# STM32F103C8T6.net
KiCad netlist of a schematic drawn in EAGLE
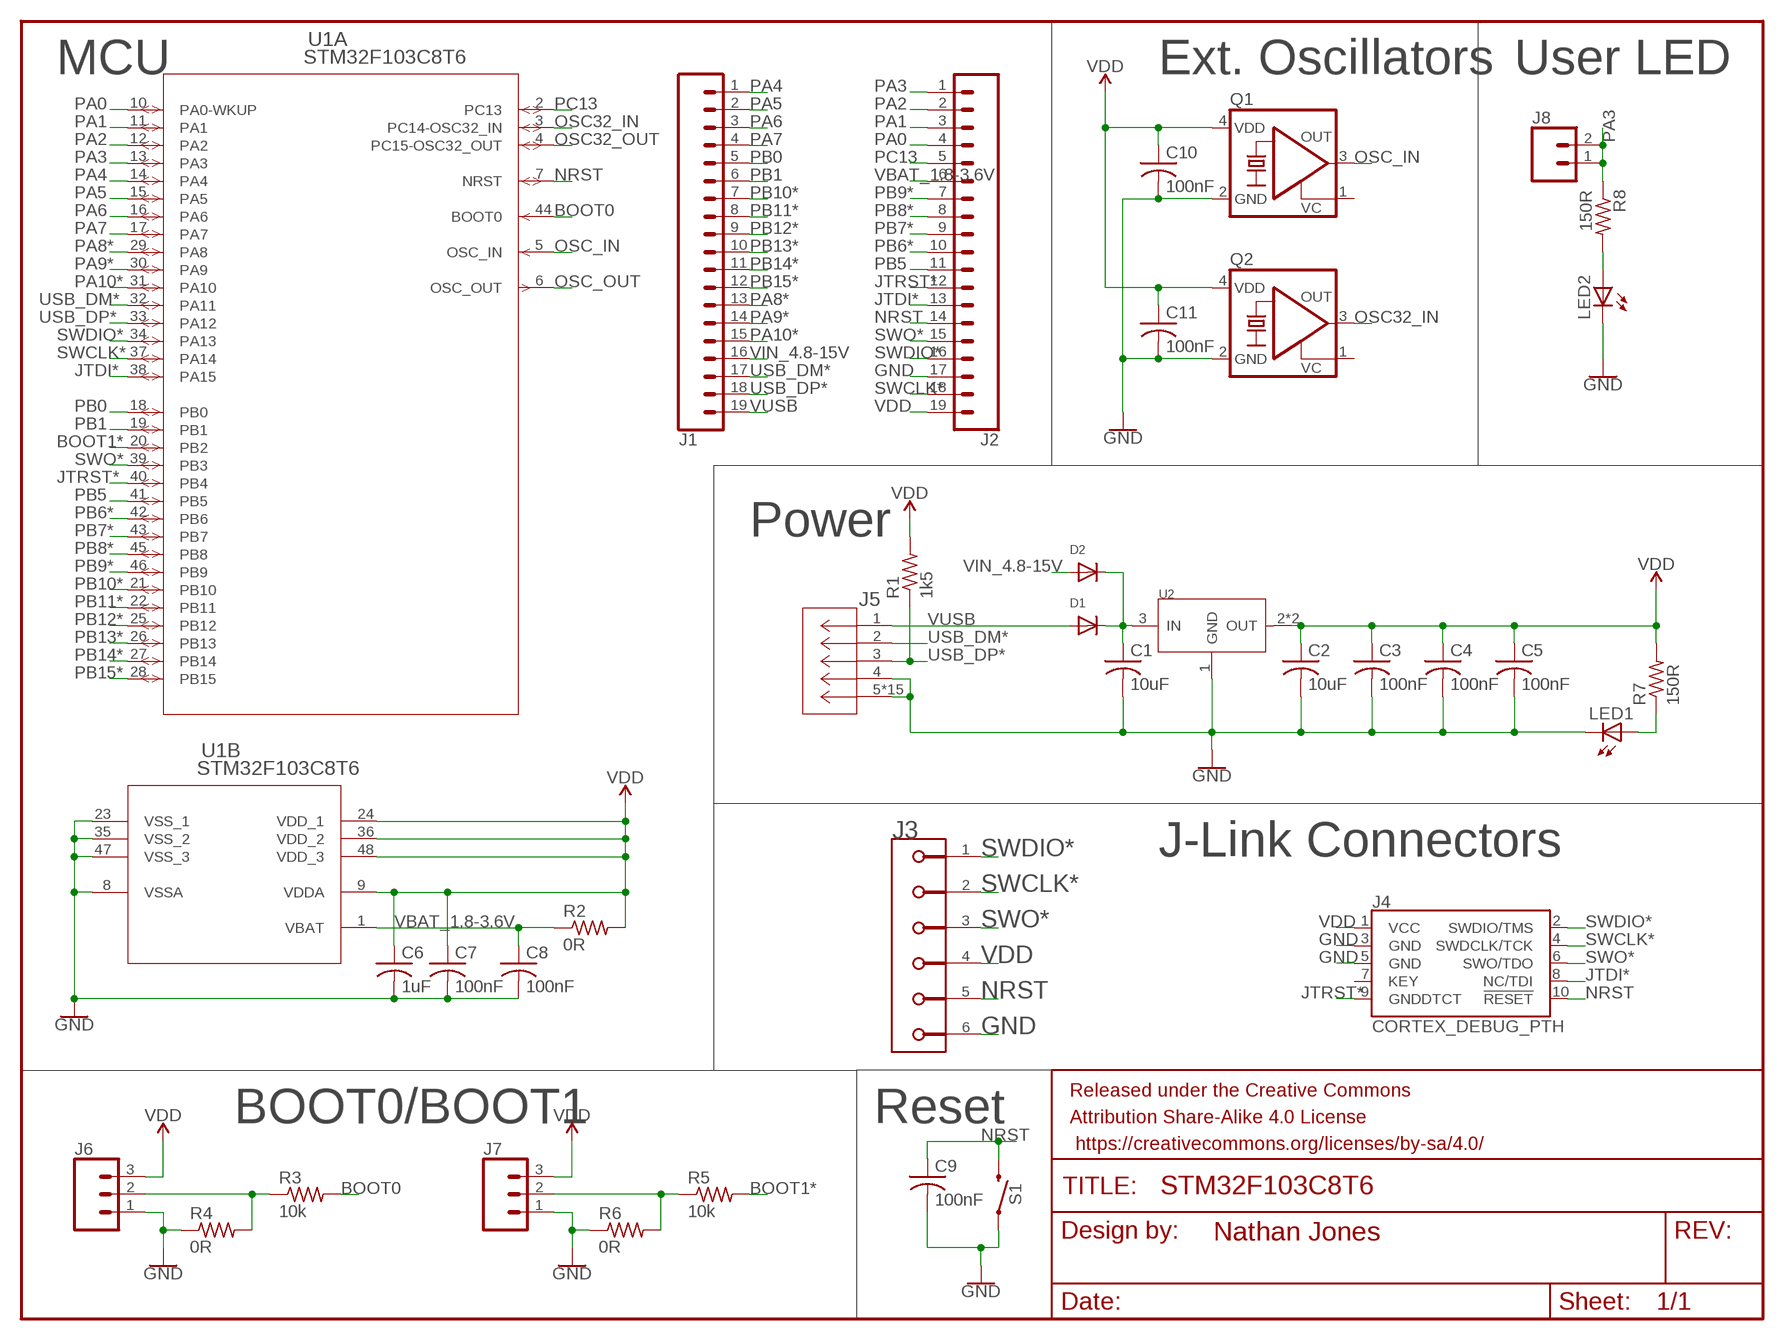
[diagram p0: schematic, sheet 1]

(export (version "E")
  (design (tool "Eeschema 10.0.6"))
  (components
    (comp (ref "C1")
      (value "10uF")
      (footprint "eagle-import:C0402")
      (fields (field (name "LCSC_PART") "C15525"))
      (libsource (lib "eagle-import") (part "C-USC0402"))
    )
    (comp (ref "C2")
      (value "10uF")
      (footprint "eagle-import:C0402")
      (fields (field (name "LCSC_PART") "C15525"))
      (libsource (lib "eagle-import") (part "C-USC0402"))
    )
    (comp (ref "C3")
      (value "100nF")
      (footprint "eagle-import:C0402")
      (fields (field (name "LCSC_PART") "C1525"))
      (libsource (lib "eagle-import") (part "C-USC0402"))
    )
    (comp (ref "C4")
      (value "100nF")
      (footprint "eagle-import:C0402")
      (fields (field (name "LCSC_PART") "C1525"))
      (libsource (lib "eagle-import") (part "C-USC0402"))
    )
    (comp (ref "C5")
      (value "100nF")
      (footprint "eagle-import:C0402")
      (fields (field (name "LCSC_PART") "C1525"))
      (libsource (lib "eagle-import") (part "C-USC0402"))
    )
    (comp (ref "C6")
      (value "1uF")
      (footprint "eagle-import:C0402")
      (fields (field (name "LCSC_PART") "C52923"))
      (libsource (lib "eagle-import") (part "C-USC0402"))
    )
    (comp (ref "C7")
      (value "100nF")
      (footprint "eagle-import:C0402")
      (fields (field (name "LCSC_PART") "C1525"))
      (libsource (lib "eagle-import") (part "C-USC0402"))
    )
    (comp (ref "C8")
      (value "100nF")
      (footprint "eagle-import:C0402")
      (fields (field (name "LCSC_PART") "C1525"))
      (libsource (lib "eagle-import") (part "C-USC0402"))
    )
    (comp (ref "C9")
      (value "100nF")
      (footprint "eagle-import:C0402")
      (fields (field (name "LCSC_PART") "C1525"))
      (libsource (lib "eagle-import") (part "C-USC0402"))
    )
    (comp (ref "C10")
      (value "100nF")
      (footprint "eagle-import:C0402")
      (fields (field (name "LCSC_PART") "C1525"))
      (libsource (lib "eagle-import") (part "C-USC0402"))
    )
    (comp (ref "C11")
      (value "100nF")
      (footprint "eagle-import:C0402")
      (fields (field (name "LCSC_PART") "C1525"))
      (libsource (lib "eagle-import") (part "C-USC0402"))
    )
    (comp (ref "D1")
      (value "DIODESOD-123")
      (footprint "eagle-import:SOD-123")
      (fields (field (name "LCSC_PART") "C8598"))
      (libsource (lib "eagle-import") (part "DIODESOD-123"))
    )
    (comp (ref "D2")
      (value "DIODESOD-123")
      (footprint "eagle-import:SOD-123")
      (fields (field (name "LCSC_PART") "C8598"))
      (libsource (lib "eagle-import") (part "DIODESOD-123"))
    )
    (comp (ref "FRAME2")
      (value "FRAME-LETTERNO_PACKAGE")
      (footprint "eagle-import:DUMMY")
      (fields (field (name "DESIGNER") "Nobody") (field (name "DESIGNER_1") "Nathan Jones"))
      (libsource (lib "eagle-import") (part "FRAME-LETTERNO_PACKAGE"))
    )
    (comp (ref "J1")
      (value "CONN_191X19_NO_SILK")
      (footprint "eagle-import:1X19_NO_SILK")
      (libsource (lib "eagle-import") (part "CONN_191X19_NO_SILK"))
    )
    (comp (ref "J2")
      (value "CONN_191X19_NO_SILK")
      (footprint "eagle-import:1X19_NO_SILK")
      (libsource (lib "eagle-import") (part "CONN_191X19_NO_SILK"))
    )
    (comp (ref "J3")
      (value "AVX_6-PIN_009159006061916")
      (footprint "eagle-import:AVX_6-PIN_009159006061916_0")
      (libsource (lib "eagle-import") (part "AVX_6-PIN_009159006061916"))
    )
    (comp (ref "J4")
      (value "CORTEX_DEBUG_PTH")
      (footprint "eagle-import:2X5-PTH-1.27MM")
      (libsource (lib "eagle-import") (part "CORTEX_DEBUG_PTH"))
    )
    (comp (ref "J5")
      (value "10118194-0001LF")
      (footprint "eagle-import:CONN_10118194-0001LF_AMP")
      (fields (field (name "COPYRIGHT") "Copyright (C) 2018 Accelerated Designs. All rights reserved"))
      (libsource (lib "eagle-import") (part "10118194-0001LF"))
    )
    (comp (ref "J6")
      (value "CONN_031X03_NO_SILK")
      (footprint "eagle-import:1X03_NO_SILK")
      (libsource (lib "eagle-import") (part "CONN_031X03_NO_SILK"))
    )
    (comp (ref "J7")
      (value "CONN_031X03_NO_SILK")
      (footprint "eagle-import:1X03_NO_SILK")
      (libsource (lib "eagle-import") (part "CONN_031X03_NO_SILK"))
    )
    (comp (ref "J8")
      (value "CONN_021X02_NO_SILK")
      (footprint "eagle-import:1X02_NO_SILK")
      (libsource (lib "eagle-import") (part "CONN_021X02_NO_SILK"))
    )
    (comp (ref "LED1")
      (value "LEDCHIPLED_0603")
      (footprint "eagle-import:CHIPLED_0603")
      (fields (field (name "LCSC_PART") "C72041"))
      (libsource (lib "eagle-import") (part "LEDCHIPLED_0603"))
    )
    (comp (ref "LED2")
      (value "LEDCHIPLED_0603")
      (footprint "eagle-import:CHIPLED_0603")
      (fields (field (name "LCSC_PART") "C72038"))
      (libsource (lib "eagle-import") (part "LEDCHIPLED_0603"))
    )
    (comp (ref "Q1")
      (value "KXO-VCXO-CMOS_4")
      (footprint "eagle-import:3.2X2.5_KXO-84-TCXO")
      (fields (field (name "LCSC_PART") "C39097"))
      (libsource (lib "eagle-import") (part "KXO-VCXO-CMOS_4"))
    )
    (comp (ref "Q2")
      (value "KXO-VCXO-CMOS_4")
      (footprint "eagle-import:3.2X2.5_KXO-84-TCXO")
      (fields (field (name "LCSC_PART") "C387415"))
      (libsource (lib "eagle-import") (part "KXO-VCXO-CMOS_4"))
    )
    (comp (ref "R1")
      (value "1k5")
      (footprint "eagle-import:R0402")
      (fields (field (name "LCSC_PART") "C25867"))
      (libsource (lib "eagle-import") (part "R-US_R0402"))
    )
    (comp (ref "R2")
      (value "0R")
      (footprint "eagle-import:R0402")
      (fields (field (name "LCSC_PART") "C17168"))
      (libsource (lib "eagle-import") (part "R-US_R0402"))
    )
    (comp (ref "R3")
      (value "10k")
      (footprint "eagle-import:R0402")
      (fields (field (name "LCSC_PART") "C25744"))
      (libsource (lib "eagle-import") (part "R-US_R0402"))
    )
    (comp (ref "R4")
      (value "0R")
      (footprint "eagle-import:R0402")
      (fields (field (name "LCSC_PART") "C17168"))
      (libsource (lib "eagle-import") (part "R-US_R0402"))
    )
    (comp (ref "R5")
      (value "10k")
      (footprint "eagle-import:R0402")
      (fields (field (name "LCSC_PART") "C25744"))
      (libsource (lib "eagle-import") (part "R-US_R0402"))
    )
    (comp (ref "R6")
      (value "0R")
      (footprint "eagle-import:R0402")
      (fields (field (name "LCSC_PART") "C17168"))
      (libsource (lib "eagle-import") (part "R-US_R0402"))
    )
    (comp (ref "R7")
      (value "150R")
      (footprint "eagle-import:R0402")
      (fields (field (name "LCSC_PART") "C25082"))
      (libsource (lib "eagle-import") (part "R-US_R0402"))
    )
    (comp (ref "R8")
      (value "150R")
      (footprint "eagle-import:R0402")
      (fields (field (name "LCSC_PART") "C25082"))
      (libsource (lib "eagle-import") (part "R-US_R0402"))
    )
    (comp (ref "S1")
      (value "MOMENTARY-SWITCH-SPST-SMD-5.2-REDUNDANT")
      (footprint "eagle-import:TACTILE_SWITCH_SMD_5.2MM")
      (fields (field (name "LCSC_PART") "C318884"))
      (libsource (lib "eagle-import") (part "MOMENTARY-SWITCH-SPST-SMD-5.2-REDUNDANT"))
    )
    (comp (ref "U1")
      (value "STM32F103C8T6")
      (footprint "eagle-import:LQFP48-7X7MM")
      (fields
        (field (name "LCSC_PART") "C94046")
        (field (name "COPYRIGHT") "Copyright (C) 2018 Accelerated Designs. All rights reserved")
      )
      (libsource (lib "eagle-import") (part "STM32F103C8T6"))
    )
    (comp (ref "U2")
      (value "CJT1117-3.3-SOT223")
      (footprint "eagle-import:SOT-223")
      (fields (field (name "MPN") "CJT1117-3.3") (field (name "LCSC_PART") "C6186"))
      (libsource (lib "eagle-import") (part "PMIC-CJT1117-3.3(SOT223)"))
    )
  )
  (nets
    (net (code "1") (name "/BOOT0") (class "Default")
      (node (ref "R3") (pin "2") (pinfunction "2_2") (pintype "passive"))
      (node (ref "U1") (pin "44") (pinfunction "BOOT0_44") (pintype "input"))
    )
    (net (code "2") (name "/BOOT1*") (class "Default")
      (node (ref "R5") (pin "2") (pinfunction "2_2") (pintype "passive"))
      (node (ref "U1") (pin "20") (pinfunction "PB2_20") (pintype "bidirectional"))
    )
    (net (code "3") (name "/JTDI*") (class "Default")
      (node (ref "J2") (pin "13") (pinfunction "13_13") (pintype "passive"))
      (node (ref "J4") (pin "8") (pinfunction "NC/TDI_8") (pintype "bidirectional"))
      (node (ref "U1") (pin "38") (pinfunction "PA15_38") (pintype "bidirectional"))
    )
    (net (code "4") (name "/JTRST*") (class "Default")
      (node (ref "J2") (pin "12") (pinfunction "12_12") (pintype "passive"))
      (node (ref "J4") (pin "9") (pinfunction "GNDDTCT_9") (pintype "bidirectional"))
      (node (ref "U1") (pin "40") (pinfunction "PB4_40") (pintype "bidirectional"))
    )
    (net (code "5") (name "/NRST") (class "Default")
      (node (ref "C9") (pin "1") (pinfunction "1_1") (pintype "passive"))
      (node (ref "J2") (pin "14") (pinfunction "14_14") (pintype "passive"))
      (node (ref "J3") (pin "5") (pinfunction "5_5") (pintype "bidirectional"))
      (node (ref "J4") (pin "10") (pinfunction "~{RESET}_10") (pintype "bidirectional"))
      (node (ref "S1") (pin "3") (pinfunction "2_3") (pintype "passive"))
      (node (ref "S1") (pin "4") (pinfunction "2_4") (pintype "passive"))
      (node (ref "U1") (pin "7") (pinfunction "NRST_7") (pintype "bidirectional"))
    )
    (net (code "6") (name "/OSC32_IN") (class "Default")
      (node (ref "Q2") (pin "3") (pinfunction "OUT_3") (pintype "output"))
      (node (ref "U1") (pin "3") (pinfunction "PC14-OSC32_IN_3") (pintype "bidirectional"))
    )
    (net (code "7") (name "/OSC32_OUT") (class "Default")
      (node (ref "U1") (pin "4") (pinfunction "PC15-OSC32_OUT_4") (pintype "bidirectional"))
    )
    (net (code "8") (name "/OSC_IN") (class "Default")
      (node (ref "Q1") (pin "3") (pinfunction "OUT_3") (pintype "output"))
      (node (ref "U1") (pin "5") (pinfunction "OSC_IN_5") (pintype "input"))
    )
    (net (code "9") (name "/OSC_OUT") (class "Default")
      (node (ref "U1") (pin "6") (pinfunction "OSC_OUT_6") (pintype "output"))
    )
    (net (code "10") (name "/PA0") (class "Default")
      (node (ref "J2") (pin "4") (pinfunction "4_4") (pintype "passive"))
      (node (ref "U1") (pin "10") (pinfunction "PA0-WKUP_10") (pintype "bidirectional"))
    )
    (net (code "11") (name "/PA1") (class "Default")
      (node (ref "J2") (pin "3") (pinfunction "3_3") (pintype "passive"))
      (node (ref "U1") (pin "11") (pinfunction "PA1_11") (pintype "bidirectional"))
    )
    (net (code "12") (name "/PA2") (class "Default")
      (node (ref "J2") (pin "2") (pinfunction "2_2") (pintype "passive"))
      (node (ref "U1") (pin "12") (pinfunction "PA2_12") (pintype "bidirectional"))
    )
    (net (code "13") (name "/PA3") (class "Default")
      (node (ref "J2") (pin "1") (pinfunction "1_1") (pintype "passive"))
      (node (ref "J8") (pin "1") (pinfunction "1_1") (pintype "passive"))
      (node (ref "J8") (pin "2") (pinfunction "2_2") (pintype "passive"))
      (node (ref "R8") (pin "1") (pinfunction "1_1") (pintype "passive"))
      (node (ref "U1") (pin "13") (pinfunction "PA3_13") (pintype "bidirectional"))
    )
    (net (code "14") (name "/PA4") (class "Default")
      (node (ref "J1") (pin "1") (pinfunction "1_1") (pintype "passive"))
      (node (ref "U1") (pin "14") (pinfunction "PA4_14") (pintype "bidirectional"))
    )
    (net (code "15") (name "/PA5") (class "Default")
      (node (ref "J1") (pin "2") (pinfunction "2_2") (pintype "passive"))
      (node (ref "U1") (pin "15") (pinfunction "PA5_15") (pintype "bidirectional"))
    )
    (net (code "16") (name "/PA6") (class "Default")
      (node (ref "J1") (pin "3") (pinfunction "3_3") (pintype "passive"))
      (node (ref "U1") (pin "16") (pinfunction "PA6_16") (pintype "bidirectional"))
    )
    (net (code "17") (name "/PA7") (class "Default")
      (node (ref "J1") (pin "4") (pinfunction "4_4") (pintype "passive"))
      (node (ref "U1") (pin "17") (pinfunction "PA7_17") (pintype "bidirectional"))
    )
    (net (code "18") (name "/PA8*") (class "Default")
      (node (ref "J1") (pin "13") (pinfunction "13_13") (pintype "passive"))
      (node (ref "U1") (pin "29") (pinfunction "PA8_29") (pintype "bidirectional"))
    )
    (net (code "19") (name "/PA9*") (class "Default")
      (node (ref "J1") (pin "14") (pinfunction "14_14") (pintype "passive"))
      (node (ref "U1") (pin "30") (pinfunction "PA9_30") (pintype "bidirectional"))
    )
    (net (code "20") (name "/PA10*") (class "Default")
      (node (ref "J1") (pin "15") (pinfunction "15_15") (pintype "passive"))
      (node (ref "U1") (pin "31") (pinfunction "PA10_31") (pintype "bidirectional"))
    )
    (net (code "21") (name "/PB0") (class "Default")
      (node (ref "J1") (pin "5") (pinfunction "5_5") (pintype "passive"))
      (node (ref "U1") (pin "18") (pinfunction "PB0_18") (pintype "bidirectional"))
    )
    (net (code "22") (name "/PB1") (class "Default")
      (node (ref "J1") (pin "6") (pinfunction "6_6") (pintype "passive"))
      (node (ref "U1") (pin "19") (pinfunction "PB1_19") (pintype "bidirectional"))
    )
    (net (code "23") (name "/PB5") (class "Default")
      (node (ref "J2") (pin "11") (pinfunction "11_11") (pintype "passive"))
      (node (ref "U1") (pin "41") (pinfunction "PB5_41") (pintype "bidirectional"))
    )
    (net (code "24") (name "/PB6*") (class "Default")
      (node (ref "J2") (pin "10") (pinfunction "10_10") (pintype "passive"))
      (node (ref "U1") (pin "42") (pinfunction "PB6_42") (pintype "bidirectional"))
    )
    (net (code "25") (name "/PB7*") (class "Default")
      (node (ref "J2") (pin "9") (pinfunction "9_9") (pintype "passive"))
      (node (ref "U1") (pin "43") (pinfunction "PB7_43") (pintype "bidirectional"))
    )
    (net (code "26") (name "/PB8*") (class "Default")
      (node (ref "J2") (pin "8") (pinfunction "8_8") (pintype "passive"))
      (node (ref "U1") (pin "45") (pinfunction "PB8_45") (pintype "bidirectional"))
    )
    (net (code "27") (name "/PB9*") (class "Default")
      (node (ref "J2") (pin "7") (pinfunction "7_7") (pintype "passive"))
      (node (ref "U1") (pin "46") (pinfunction "PB9_46") (pintype "bidirectional"))
    )
    (net (code "28") (name "/PB10*") (class "Default")
      (node (ref "J1") (pin "7") (pinfunction "7_7") (pintype "passive"))
      (node (ref "U1") (pin "21") (pinfunction "PB10_21") (pintype "bidirectional"))
    )
    (net (code "29") (name "/PB11*") (class "Default")
      (node (ref "J1") (pin "8") (pinfunction "8_8") (pintype "passive"))
      (node (ref "U1") (pin "22") (pinfunction "PB11_22") (pintype "bidirectional"))
    )
    (net (code "30") (name "/PB12*") (class "Default")
      (node (ref "J1") (pin "9") (pinfunction "9_9") (pintype "passive"))
      (node (ref "U1") (pin "25") (pinfunction "PB12_25") (pintype "bidirectional"))
    )
    (net (code "31") (name "/PB13*") (class "Default")
      (node (ref "J1") (pin "10") (pinfunction "10_10") (pintype "passive"))
      (node (ref "U1") (pin "26") (pinfunction "PB13_26") (pintype "bidirectional"))
    )
    (net (code "32") (name "/PB14*") (class "Default")
      (node (ref "J1") (pin "11") (pinfunction "11_11") (pintype "passive"))
      (node (ref "U1") (pin "27") (pinfunction "PB14_27") (pintype "bidirectional"))
    )
    (net (code "33") (name "/PB15*") (class "Default")
      (node (ref "J1") (pin "12") (pinfunction "12_12") (pintype "passive"))
      (node (ref "U1") (pin "28") (pinfunction "PB15_28") (pintype "bidirectional"))
    )
    (net (code "34") (name "/PC13") (class "Default")
      (node (ref "J2") (pin "5") (pinfunction "5_5") (pintype "passive"))
      (node (ref "U1") (pin "2") (pinfunction "PC13_2") (pintype "bidirectional"))
    )
    (net (code "35") (name "/SWCLK*") (class "Default")
      (node (ref "J2") (pin "18") (pinfunction "18_18") (pintype "passive"))
      (node (ref "J3") (pin "2") (pinfunction "2_2") (pintype "bidirectional"))
      (node (ref "J4") (pin "4") (pinfunction "SWDCLK/TCK_4") (pintype "bidirectional"))
      (node (ref "U1") (pin "37") (pinfunction "PA14_37") (pintype "bidirectional"))
    )
    (net (code "36") (name "/SWDIO*") (class "Default")
      (node (ref "J2") (pin "16") (pinfunction "16_16") (pintype "passive"))
      (node (ref "J3") (pin "1") (pinfunction "1_1") (pintype "bidirectional"))
      (node (ref "J4") (pin "2") (pinfunction "SWDIO/TMS_2") (pintype "bidirectional"))
      (node (ref "U1") (pin "34") (pinfunction "PA13_34") (pintype "bidirectional"))
    )
    (net (code "37") (name "/SWO*") (class "Default")
      (node (ref "J2") (pin "15") (pinfunction "15_15") (pintype "passive"))
      (node (ref "J3") (pin "3") (pinfunction "3_3") (pintype "bidirectional"))
      (node (ref "J4") (pin "6") (pinfunction "SWO/TDO_6") (pintype "bidirectional"))
      (node (ref "U1") (pin "39") (pinfunction "PB3_39") (pintype "bidirectional"))
    )
    (net (code "38") (name "/USB_DM*") (class "Default")
      (node (ref "J1") (pin "17") (pinfunction "17_17") (pintype "passive"))
      (node (ref "J5") (pin "2") (pinfunction "2_2") (pintype "passive"))
      (node (ref "U1") (pin "32") (pinfunction "PA11_32") (pintype "bidirectional"))
    )
    (net (code "39") (name "/USB_DP*") (class "Default")
      (node (ref "J1") (pin "18") (pinfunction "18_18") (pintype "passive"))
      (node (ref "J5") (pin "3") (pinfunction "3_3") (pintype "passive"))
      (node (ref "R1") (pin "1") (pinfunction "1_1") (pintype "passive"))
      (node (ref "U1") (pin "33") (pinfunction "PA12_33") (pintype "bidirectional"))
    )
    (net (code "40") (name "/VBAT_1.8-3.6V") (class "Default")
      (node (ref "C8") (pin "1") (pinfunction "1_1") (pintype "passive"))
      (node (ref "J2") (pin "6") (pinfunction "6_6") (pintype "passive"))
      (node (ref "R2") (pin "1") (pinfunction "1_1") (pintype "passive"))
      (node (ref "U1") (pin "1") (pinfunction "VBAT_1") (pintype "power_in"))
    )
    (net (code "41") (name "/VIN_4.8-15V") (class "Default")
      (node (ref "D2") (pin "A") (pinfunction "A_A") (pintype "passive"))
      (node (ref "J1") (pin "16") (pinfunction "16_16") (pintype "passive"))
    )
    (net (code "42") (name "/VUSB") (class "Default")
      (node (ref "D1") (pin "A") (pinfunction "A_A") (pintype "passive"))
      (node (ref "J1") (pin "19") (pinfunction "19_19") (pintype "passive"))
      (node (ref "J5") (pin "1") (pinfunction "1_1") (pintype "passive"))
    )
    (net (code "43") (name "GND") (class "Default")
      (node (ref "C1") (pin "2") (pinfunction "2_2") (pintype "passive"))
      (node (ref "C10") (pin "2") (pinfunction "2_2") (pintype "passive"))
      (node (ref "C11") (pin "2") (pinfunction "2_2") (pintype "passive"))
      (node (ref "C2") (pin "2") (pinfunction "2_2") (pintype "passive"))
      (node (ref "C3") (pin "2") (pinfunction "2_2") (pintype "passive"))
      (node (ref "C4") (pin "2") (pinfunction "2_2") (pintype "passive"))
      (node (ref "C5") (pin "2") (pinfunction "2_2") (pintype "passive"))
      (node (ref "C6") (pin "2") (pinfunction "2_2") (pintype "passive"))
      (node (ref "C7") (pin "2") (pinfunction "2_2") (pintype "passive"))
      (node (ref "C8") (pin "2") (pinfunction "2_2") (pintype "passive"))
      (node (ref "C9") (pin "2") (pinfunction "2_2") (pintype "passive"))
      (node (ref "J2") (pin "17") (pinfunction "17_17") (pintype "passive"))
      (node (ref "J3") (pin "6") (pinfunction "6_6") (pintype "bidirectional"))
      (node (ref "J4") (pin "3") (pinfunction "GND_3") (pintype "bidirectional"))
      (node (ref "J4") (pin "5") (pinfunction "GND_5") (pintype "bidirectional"))
      (node (ref "J5") (pin "10") (pinfunction "5_10") (pintype "passive"))
      (node (ref "J5") (pin "11") (pinfunction "5_11") (pintype "passive"))
      (node (ref "J5") (pin "4") (pinfunction "4_4") (pintype "passive"))
      (node (ref "J5") (pin "5") (pinfunction "5_5") (pintype "passive"))
      (node (ref "J5") (pin "S_1") (pinfunction "5_S_1") (pintype "passive"))
      (node (ref "J5") (pin "S_1_H1") (pinfunction "5_S_1_H1") (pintype "passive"))
      (node (ref "J5") (pin "S_1_H2") (pinfunction "5_S_1_H2") (pintype "passive"))
      (node (ref "J5") (pin "S_2") (pinfunction "5_S_2") (pintype "passive"))
      (node (ref "J5") (pin "S_2_H1") (pinfunction "5_S_2_H1") (pintype "passive"))
      (node (ref "J5") (pin "S_2_H2") (pinfunction "5_S_2_H2") (pintype "passive"))
      (node (ref "J5") (pin "S_3") (pinfunction "5_S_3") (pintype "passive"))
      (node (ref "J5") (pin "S_3_H1") (pinfunction "5_S_3_H1") (pintype "passive"))
      (node (ref "J5") (pin "S_3_H2") (pinfunction "5_S_3_H2") (pintype "passive"))
      (node (ref "J5") (pin "S_4") (pinfunction "5_S_4") (pintype "passive"))
      (node (ref "J5") (pin "S_4_H1") (pinfunction "5_S_4_H1") (pintype "passive"))
      (node (ref "J5") (pin "S_4_H2") (pinfunction "5_S_4_H2") (pintype "passive"))
      (node (ref "J6") (pin "1") (pinfunction "1_1") (pintype "passive"))
      (node (ref "J7") (pin "1") (pinfunction "1_1") (pintype "passive"))
      (node (ref "LED1") (pin "C") (pinfunction "C_C") (pintype "passive"))
      (node (ref "LED2") (pin "C") (pinfunction "C_C") (pintype "passive"))
      (node (ref "Q1") (pin "2") (pinfunction "GND_2") (pintype "power_in"))
      (node (ref "Q2") (pin "2") (pinfunction "GND_2") (pintype "power_in"))
      (node (ref "R4") (pin "1") (pinfunction "1_1") (pintype "passive"))
      (node (ref "R6") (pin "1") (pinfunction "1_1") (pintype "passive"))
      (node (ref "S1") (pin "1") (pinfunction "1_1") (pintype "passive"))
      (node (ref "S1") (pin "2") (pinfunction "1_2") (pintype "passive"))
      (node (ref "U1") (pin "23") (pinfunction "VSS_1_23") (pintype "power_in"))
      (node (ref "U1") (pin "35") (pinfunction "VSS_2_35") (pintype "power_in"))
      (node (ref "U1") (pin "47") (pinfunction "VSS_3_47") (pintype "power_in"))
      (node (ref "U1") (pin "8") (pinfunction "VSSA_8") (pintype "power_in"))
      (node (ref "U2") (pin "1") (pinfunction "GND_1") (pintype "bidirectional"))
    )
    (net (code "44") (name "Net-(J6-Pad2)") (class "Default")
      (node (ref "J6") (pin "2") (pinfunction "2_2") (pintype "passive"))
      (node (ref "R3") (pin "1") (pinfunction "1_1") (pintype "passive"))
      (node (ref "R4") (pin "2") (pinfunction "2_2") (pintype "passive"))
    )
    (net (code "45") (name "Net-(J7-Pad2)") (class "Default")
      (node (ref "J7") (pin "2") (pinfunction "2_2") (pintype "passive"))
      (node (ref "R5") (pin "1") (pinfunction "1_1") (pintype "passive"))
      (node (ref "R6") (pin "2") (pinfunction "2_2") (pintype "passive"))
    )
    (net (code "46") (name "Net-(LED1-PadA)") (class "Default")
      (node (ref "LED1") (pin "A") (pinfunction "A_A") (pintype "passive"))
      (node (ref "R7") (pin "1") (pinfunction "1_1") (pintype "passive"))
    )
    (net (code "47") (name "Net-(LED2-PadA)") (class "Default")
      (node (ref "LED2") (pin "A") (pinfunction "A_A") (pintype "passive"))
      (node (ref "R8") (pin "2") (pinfunction "2_2") (pintype "passive"))
    )
    (net (code "48") (name "Net-(U2-IN)") (class "Default")
      (node (ref "C1") (pin "1") (pinfunction "1_1") (pintype "passive"))
      (node (ref "D1") (pin "C") (pinfunction "C_C") (pintype "passive"))
      (node (ref "D2") (pin "C") (pinfunction "C_C") (pintype "passive"))
      (node (ref "U2") (pin "3") (pinfunction "IN_3") (pintype "bidirectional"))
    )
    (net (code "49") (name "VDD") (class "Default")
      (node (ref "C10") (pin "1") (pinfunction "1_1") (pintype "passive"))
      (node (ref "C11") (pin "1") (pinfunction "1_1") (pintype "passive"))
      (node (ref "C2") (pin "1") (pinfunction "1_1") (pintype "passive"))
      (node (ref "C3") (pin "1") (pinfunction "1_1") (pintype "passive"))
      (node (ref "C4") (pin "1") (pinfunction "1_1") (pintype "passive"))
      (node (ref "C5") (pin "1") (pinfunction "1_1") (pintype "passive"))
      (node (ref "C6") (pin "1") (pinfunction "1_1") (pintype "passive"))
      (node (ref "C7") (pin "1") (pinfunction "1_1") (pintype "passive"))
      (node (ref "J2") (pin "19") (pinfunction "19_19") (pintype "passive"))
      (node (ref "J3") (pin "4") (pinfunction "4_4") (pintype "bidirectional"))
      (node (ref "J4") (pin "1") (pinfunction "VCC_1") (pintype "bidirectional"))
      (node (ref "J6") (pin "3") (pinfunction "3_3") (pintype "passive"))
      (node (ref "J7") (pin "3") (pinfunction "3_3") (pintype "passive"))
      (node (ref "Q1") (pin "4") (pinfunction "VDD_4") (pintype "power_in"))
      (node (ref "Q2") (pin "4") (pinfunction "VDD_4") (pintype "power_in"))
      (node (ref "R1") (pin "2") (pinfunction "2_2") (pintype "passive"))
      (node (ref "R2") (pin "2") (pinfunction "2_2") (pintype "passive"))
      (node (ref "R7") (pin "2") (pinfunction "2_2") (pintype "passive"))
      (node (ref "U1") (pin "24") (pinfunction "VDD_1_24") (pintype "power_in"))
      (node (ref "U1") (pin "36") (pinfunction "VDD_2_36") (pintype "power_in"))
      (node (ref "U1") (pin "48") (pinfunction "VDD_3_48") (pintype "power_in"))
      (node (ref "U1") (pin "9") (pinfunction "VDDA_9") (pintype "power_in"))
      (node (ref "U2") (pin "2") (pinfunction "OUT_2") (pintype "bidirectional"))
      (node (ref "U2") (pin "TER") (pinfunction "OUT_TER") (pintype "bidirectional"))
    )
    (net (code "50") (name "unconnected-(J4-KEY-Pad7)") (class "Default")
      (node (ref "J4") (pin "7") (pinfunction "KEY_7") (pintype "bidirectional"))
    )
    (net (code "51") (name "unconnected-(Q1-VC-Pad1)") (class "Default")
      (node (ref "Q1") (pin "1") (pinfunction "VC_1") (pintype "input"))
    )
    (net (code "52") (name "unconnected-(Q2-VC-Pad1)") (class "Default")
      (node (ref "Q2") (pin "1") (pinfunction "VC_1") (pintype "input"))
    )
  )
)
